# BRAINS.net
KiCad netlist of a schematic drawn in Altium Designer
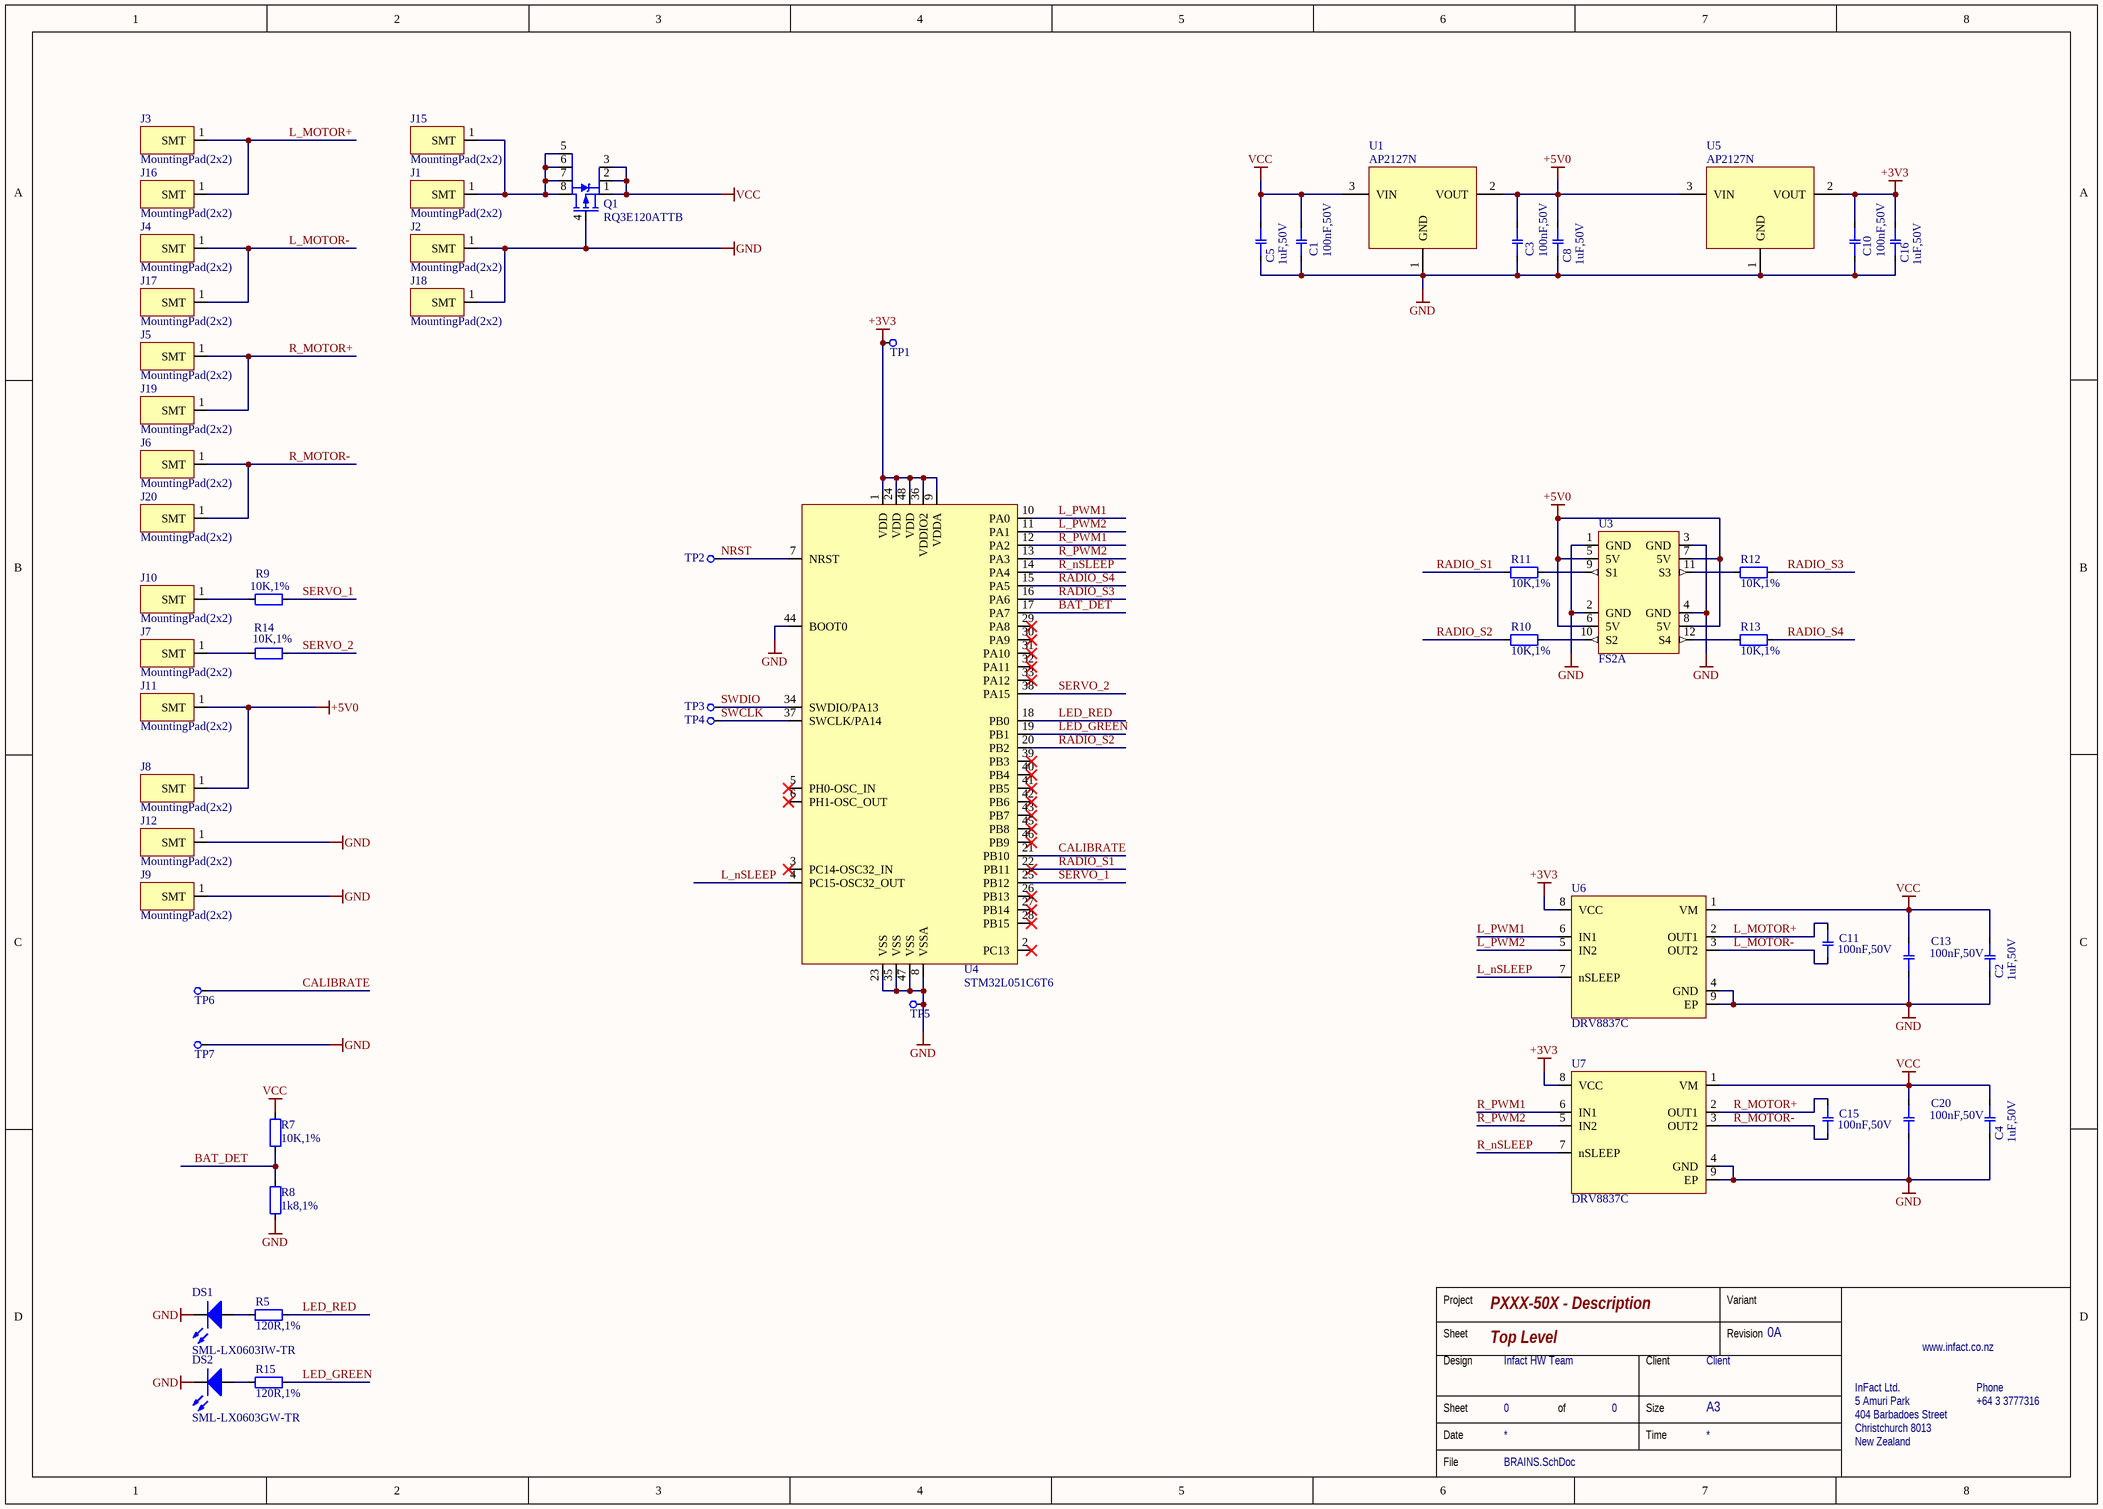
[diagram p0: BRAINS.SchDoc]

(export (version "E")
  (design (tool "Eeschema 10.0.6"))
  (components
    (comp (ref "C1")
      (value "100nF,50V")
      (footprint "CAPC1005X05N_0402")
      (description "CAP CER 100nF 50V X7R 0402")
      (fields (field (name "MANUFACTURER") "Taiyo Yuden") (field (name "TOLERANCE") "10%"))
      (libsource (lib "library") (part "CAP-NP_1"))
    )
    (comp (ref "C2")
      (value "1uF,50V")
      (footprint "CAPC1005X05N_0402")
      (description "CAP CER 1UF 50V X5R 0402")
      (fields (field (name "MANUFACTURER") "Taiyo Yuden") (field (name "TOLERANCE") "20%"))
      (libsource (lib "library") (part "CAP-NP_1"))
    )
    (comp (ref "C3")
      (value "100nF,50V")
      (footprint "CAPC1005X05N_0402")
      (description "CAP CER 100nF 50V X7R 0402")
      (fields (field (name "MANUFACTURER") "Taiyo Yuden") (field (name "TOLERANCE") "10%"))
      (libsource (lib "library") (part "CAP-NP_1"))
    )
    (comp (ref "C4")
      (value "1uF,50V")
      (footprint "CAPC1005X05N_0402")
      (description "CAP CER 1UF 50V X5R 0402")
      (fields (field (name "MANUFACTURER") "Taiyo Yuden") (field (name "TOLERANCE") "20%"))
      (libsource (lib "library") (part "CAP-NP_1"))
    )
    (comp (ref "C5")
      (value "1uF,50V")
      (footprint "CAPC1005X05N_0402")
      (description "CAP CER 1UF 50V X5R 0402")
      (fields (field (name "MANUFACTURER") "Taiyo Yuden") (field (name "TOLERANCE") "20%"))
      (libsource (lib "library") (part "CAP-NP_1"))
    )
    (comp (ref "C8")
      (value "1uF,50V")
      (footprint "CAPC1005X05N_0402")
      (description "CAP CER 1UF 50V X5R 0402")
      (fields (field (name "MANUFACTURER") "Taiyo Yuden") (field (name "TOLERANCE") "20%"))
      (libsource (lib "library") (part "CAP-NP_1"))
    )
    (comp (ref "C10")
      (value "100nF,50V")
      (footprint "CAPC1005X05N_0402")
      (description "CAP CER 100nF 50V X7R 0402")
      (fields (field (name "MANUFACTURER") "Taiyo Yuden") (field (name "TOLERANCE") "10%"))
      (libsource (lib "library") (part "CAP-NP_1"))
    )
    (comp (ref "C11")
      (value "100nF,50V")
      (footprint "CAPC1005X05N_0402")
      (description "CAP CER 100nF 50V X7R 0402")
      (fields (field (name "MANUFACTURER") "Taiyo Yuden") (field (name "TOLERANCE") "10%"))
      (libsource (lib "library") (part "CAP-NP_1"))
    )
    (comp (ref "C13")
      (value "100nF,50V")
      (footprint "CAPC1005X05N_0402")
      (description "CAP CER 100nF 50V X7R 0402")
      (fields (field (name "MANUFACTURER") "Taiyo Yuden") (field (name "TOLERANCE") "10%"))
      (libsource (lib "library") (part "CAP-NP_1"))
    )
    (comp (ref "C15")
      (value "100nF,50V")
      (footprint "CAPC1005X05N_0402")
      (description "CAP CER 100nF 50V X7R 0402")
      (fields (field (name "MANUFACTURER") "Taiyo Yuden") (field (name "TOLERANCE") "10%"))
      (libsource (lib "library") (part "CAP-NP_1"))
    )
    (comp (ref "C16")
      (value "1uF,50V")
      (footprint "CAPC1005X05N_0402")
      (description "CAP CER 1UF 50V X5R 0402")
      (fields (field (name "MANUFACTURER") "Taiyo Yuden") (field (name "TOLERANCE") "20%"))
      (libsource (lib "library") (part "CAP-NP_1"))
    )
    (comp (ref "C20")
      (value "100nF,50V")
      (footprint "CAPC1005X05N_0402")
      (description "CAP CER 100nF 50V X7R 0402")
      (fields (field (name "MANUFACTURER") "Taiyo Yuden") (field (name "TOLERANCE") "10%"))
      (libsource (lib "library") (part "CAP-NP_1"))
    )
    (comp (ref "DS1")
      (value "SML-LX0603IW-TR")
      (footprint "LED_SML-LX0603")
      (description "LED 635NM RED DIFF 0603 SMD")
      (fields (field (name "MANUFACTURER") "Lumex Opto/Components Inc"))
      (libsource (lib "library") (part "LED_1"))
    )
    (comp (ref "DS2")
      (value "SML-LX0603GW-TR")
      (footprint "LED_SML-LX0603")
      (description "LED 565NM GRN DIFF 0603 SMD")
      (fields (field (name "MANUFACTURER") "Lumex Opto/Components Inc"))
      (libsource (lib "library") (part "LED_1"))
    )
    (comp (ref "J1")
      (value "MountingPad(2x2)")
      (footprint "MountingPad(2x2)")
      (libsource (lib "") (part "MountingPad(2x2)_1"))
    )
    (comp (ref "J2")
      (value "MountingPad(2x2)")
      (footprint "MountingPad(2x2)")
      (libsource (lib "") (part "MountingPad(2x2)_1"))
    )
    (comp (ref "J3")
      (value "MountingPad(2x2)")
      (footprint "MountingPad(2x2)")
      (libsource (lib "Schlib1") (part "MountingPad(2x2)"))
    )
    (comp (ref "J4")
      (value "MountingPad(2x2)")
      (footprint "MountingPad(2x2)")
      (libsource (lib "Schlib1") (part "MountingPad(2x2)"))
    )
    (comp (ref "J5")
      (value "MountingPad(2x2)")
      (footprint "MountingPad(2x2)")
      (libsource (lib "Schlib1") (part "MountingPad(2x2)"))
    )
    (comp (ref "J6")
      (value "MountingPad(2x2)")
      (footprint "MountingPad(2x2)")
      (libsource (lib "Schlib1") (part "MountingPad(2x2)"))
    )
    (comp (ref "J7")
      (value "MountingPad(2x2)")
      (footprint "MountingPad(2x2)")
      (libsource (lib "Schlib1") (part "MountingPad(2x2)"))
    )
    (comp (ref "J8")
      (value "MountingPad(2x2)")
      (footprint "MountingPad(2x2)")
      (libsource (lib "Schlib1") (part "MountingPad(2x2)"))
    )
    (comp (ref "J9")
      (value "MountingPad(2x2)")
      (footprint "MountingPad(2x2)")
      (libsource (lib "Schlib1") (part "MountingPad(2x2)"))
    )
    (comp (ref "J10")
      (value "MountingPad(2x2)")
      (footprint "MountingPad(2x2)")
      (libsource (lib "Schlib1") (part "MountingPad(2x2)"))
    )
    (comp (ref "J11")
      (value "MountingPad(2x2)")
      (footprint "MountingPad(2x2)")
      (libsource (lib "Schlib1") (part "MountingPad(2x2)"))
    )
    (comp (ref "J12")
      (value "MountingPad(2x2)")
      (footprint "MountingPad(2x2)")
      (libsource (lib "Schlib1") (part "MountingPad(2x2)"))
    )
    (comp (ref "J15")
      (value "MountingPad(2x2)")
      (footprint "MountingPad(2x2)")
      (libsource (lib "Schlib1") (part "MountingPad(2x2)"))
    )
    (comp (ref "J16")
      (value "MountingPad(2x2)")
      (footprint "MountingPad(2x2)")
      (libsource (lib "Schlib1") (part "MountingPad(2x2)"))
    )
    (comp (ref "J17")
      (value "MountingPad(2x2)")
      (footprint "MountingPad(2x2)")
      (libsource (lib "Schlib1") (part "MountingPad(2x2)"))
    )
    (comp (ref "J18")
      (value "MountingPad(2x2)")
      (footprint "MountingPad(2x2)")
      (libsource (lib "Schlib1") (part "MountingPad(2x2)"))
    )
    (comp (ref "J19")
      (value "MountingPad(2x2)")
      (footprint "MountingPad(2x2)")
      (libsource (lib "Schlib1") (part "MountingPad(2x2)"))
    )
    (comp (ref "J20")
      (value "MountingPad(2x2)")
      (footprint "MountingPad(2x2)")
      (libsource (lib "Schlib1") (part "MountingPad(2x2)"))
    )
    (comp (ref "Q1")
      (value "RQ3E120ATTB")
      (footprint "ROHM-HSMT8")
      (description "MOSFET P-CH 30V 12A 8HSMT")
      (fields (field (name "MANUFACTURER") "Rohm Semiconductor"))
      (libsource (lib "library") (part "MOSFET-P_5"))
    )
    (comp (ref "R5")
      (value "120R,1%")
      (footprint "RESC1005X04N_0402")
      (description "RES 120 OHM 1/16W 0402 SMD")
      (fields (field (name "MANUFACTURER") "Yageo") (field (name "POWER") "0.0625W"))
      (libsource (lib "library") (part "RESISTOR_1"))
    )
    (comp (ref "R7")
      (value "10K,1%")
      (footprint "RESC1005X04N_0402")
      (description "RES 10K OHM 1/16W 1% 0402 SMD")
      (fields (field (name "MANUFACTURER") "Yageo") (field (name "POWER") "0.0625W"))
      (libsource (lib "") (part "RESISTOR_1_1"))
    )
    (comp (ref "R8")
      (value "1k8,1%")
      (footprint "RESC1005X04N_0402")
      (description "RES 1k8 0.0625W 1% 0402 SMD")
      (fields (field (name "MANUFACTURER") "Vishay Dale") (field (name "POWER") "0.0625W"))
      (libsource (lib "") (part "RESISTOR_1_1"))
    )
    (comp (ref "R9")
      (value "10K,1%")
      (footprint "RESC1005X04N_0402")
      (description "RES 10K OHM 1/16W 1% 0402 SMD")
      (fields (field (name "MANUFACTURER") "Yageo") (field (name "POWER") "0.0625W"))
      (libsource (lib "") (part "RESISTOR_1_1"))
    )
    (comp (ref "R10")
      (value "10K,1%")
      (footprint "RESC1005X04N_0402")
      (description "RES 10K OHM 1/16W 1% 0402 SMD")
      (fields (field (name "MANUFACTURER") "Yageo") (field (name "POWER") "0.0625W"))
      (libsource (lib "library") (part "RESISTOR_1"))
    )
    (comp (ref "R11")
      (value "10K,1%")
      (footprint "RESC1005X04N_0402")
      (description "RES 10K OHM 1/16W 1% 0402 SMD")
      (fields (field (name "MANUFACTURER") "Yageo") (field (name "POWER") "0.0625W"))
      (libsource (lib "library") (part "RESISTOR_1"))
    )
    (comp (ref "R12")
      (value "10K,1%")
      (footprint "RESC1005X04N_0402")
      (description "RES 10K OHM 1/16W 1% 0402 SMD")
      (fields (field (name "MANUFACTURER") "Yageo") (field (name "POWER") "0.0625W"))
      (libsource (lib "library") (part "RESISTOR_1"))
    )
    (comp (ref "R13")
      (value "10K,1%")
      (footprint "RESC1005X04N_0402")
      (description "RES 10K OHM 1/16W 1% 0402 SMD")
      (fields (field (name "MANUFACTURER") "Yageo") (field (name "POWER") "0.0625W"))
      (libsource (lib "library") (part "RESISTOR_1"))
    )
    (comp (ref "R14")
      (value "10K,1%")
      (footprint "RESC1005X04N_0402")
      (description "RES 10K OHM 1/16W 1% 0402 SMD")
      (fields (field (name "MANUFACTURER") "Yageo") (field (name "POWER") "0.0625W"))
      (libsource (lib "") (part "RESISTOR_1_1"))
    )
    (comp (ref "R15")
      (value "120R,1%")
      (footprint "RESC1005X04N_0402")
      (description "RES 120 OHM 1/16W 0402 SMD")
      (fields (field (name "MANUFACTURER") "Yageo") (field (name "POWER") "0.0625W"))
      (libsource (lib "library") (part "RESISTOR_1"))
    )
    (comp (ref "TP1")
      (value "TP_SMT")
      (footprint "TP_100")
      (description "Test Point - SMT")
      (libsource (lib "library") (part "TP_1"))
    )
    (comp (ref "TP2")
      (value "TP_SMT")
      (footprint "TP_100")
      (description "Test Point - SMT")
      (libsource (lib "library") (part "TP_1"))
    )
    (comp (ref "TP3")
      (value "TP_SMT")
      (footprint "TP_100")
      (description "Test Point - SMT")
      (libsource (lib "library") (part "TP_1"))
    )
    (comp (ref "TP4")
      (value "TP_SMT")
      (footprint "TP_100")
      (description "Test Point - SMT")
      (libsource (lib "library") (part "TP_1"))
    )
    (comp (ref "TP5")
      (value "TP_SMT")
      (footprint "TP_100")
      (description "Test Point - SMT")
      (libsource (lib "library") (part "TP_1"))
    )
    (comp (ref "TP6")
      (value "TP_SMT")
      (footprint "TP_100")
      (description "Test Point - SMT")
      (libsource (lib "library") (part "TP_1"))
    )
    (comp (ref "TP7")
      (value "TP_SMT")
      (footprint "TP_100")
      (description "Test Point - SMT")
      (libsource (lib "library") (part "TP_1"))
    )
    (comp (ref "U1")
      (value "AP2127N")
      (footprint "SOT95P237X112-3N_SOT23")
      (description "IC REG LINEAR 3.3V 300MA SOT23")
      (fields
        (field (name "MANUFACTURER") "Diodes Incorporated")
        (field (name "MANUFACTURER PART NUMBER") "AP2127N-3.3TRG1")
      )
      (libsource (lib "library") (part "AP2127N-3.3TRG1"))
    )
    (comp (ref "U3") (value "FS2A") (footprint "FS2A") (libsource (lib "Schlib1") (part "FS2A")))
    (comp (ref "U4")
      (value "STM32L051C6T6")
      (footprint "TSQFP50P900X900X160-48N_48LQFP")
      (description "IC MCU 32BIT 32KB FLASH 48LQFP")
      (fields (field (name "MANUFACTURER") "STMicroelectronics"))
      (libsource (lib "library") (part "STM32L051_48"))
    )
    (comp (ref "U5")
      (value "AP2127N")
      (footprint "SOT95P237X112-3N_SOT23")
      (description "IC REG LINEAR 3.3V 300MA SOT23")
      (fields
        (field (name "MANUFACTURER") "Diodes Incorporated")
        (field (name "MANUFACTURER PART NUMBER") "AP2127N-3.3TRG1")
      )
      (libsource (lib "library") (part "AP2127N-3.3TRG1"))
    )
    (comp (ref "U6")
      (value "DRV8837C")
      (footprint "DFN50P200X200X80-8N")
      (description "IC HALF-BRIDGE DRVR PWM 8WSON")
      (fields
        (field (name "MANUFACTURER") "Texas Instruments")
        (field (name "MANUFACTURER PART NUMBER") "DRV8837CDSGR")
      )
      (libsource (lib "library") (part "DRV8837C"))
    )
    (comp (ref "U7")
      (value "DRV8837C")
      (footprint "DFN50P200X200X80-8N")
      (description "IC HALF-BRIDGE DRVR PWM 8WSON")
      (fields
        (field (name "MANUFACTURER") "Texas Instruments")
        (field (name "MANUFACTURER PART NUMBER") "DRV8837CDSGR")
      )
      (libsource (lib "library") (part "DRV8837C"))
    )
  )
  (nets
    (net (code "1") (name "+3V3") (class "Default")
      (node (ref "C10") (pin "2") (pinfunction "2_2") (pintype "passive"))
      (node (ref "C16") (pin "2") (pinfunction "2_2") (pintype "passive"))
      (node (ref "TP1") (pin "1") (pinfunction "1_1") (pintype "passive"))
      (node (ref "U4") (pin "1") (pinfunction "VDD_1") (pintype "passive"))
      (node (ref "U4") (pin "24") (pinfunction "VDD_24") (pintype "passive"))
      (node (ref "U4") (pin "36") (pinfunction "VDDIO2_36") (pintype "passive"))
      (node (ref "U4") (pin "48") (pinfunction "VDD_48") (pintype "passive"))
      (node (ref "U4") (pin "9") (pinfunction "VDDA_9") (pintype "passive"))
      (node (ref "U5") (pin "2") (pinfunction "VOUT_2") (pintype "passive"))
      (node (ref "U6") (pin "8") (pinfunction "VCC_8") (pintype "passive"))
      (node (ref "U7") (pin "8") (pinfunction "VCC_8") (pintype "passive"))
    )
    (net (code "2") (name "+5V0") (class "Default")
      (node (ref "C3") (pin "2") (pinfunction "2_2") (pintype "passive"))
      (node (ref "C8") (pin "2") (pinfunction "2_2") (pintype "passive"))
      (node (ref "J11") (pin "1") (pinfunction "SMT_1") (pintype "passive"))
      (node (ref "J8") (pin "1") (pinfunction "SMT_1") (pintype "passive"))
      (node (ref "U1") (pin "2") (pinfunction "VOUT_2") (pintype "passive"))
      (node (ref "U3") (pin "5") (pinfunction "5V_5") (pintype "power_in"))
      (node (ref "U3") (pin "6") (pinfunction "5V_6") (pintype "power_in"))
      (node (ref "U3") (pin "7") (pinfunction "5V_7") (pintype "power_in"))
      (node (ref "U3") (pin "8") (pinfunction "5V_8") (pintype "power_in"))
      (node (ref "U5") (pin "3") (pinfunction "VIN_3") (pintype "passive"))
    )
    (net (code "3") (name "/BAT_DET") (class "Default")
      (node (ref "R7") (pin "2") (pinfunction "2_2") (pintype "passive"))
      (node (ref "R8") (pin "1") (pinfunction "1_1") (pintype "passive"))
      (node (ref "U4") (pin "17") (pinfunction "PA7_17") (pintype "passive"))
    )
    (net (code "4") (name "/CALIBRATE") (class "Default")
      (node (ref "TP6") (pin "1") (pinfunction "1_1") (pintype "passive"))
      (node (ref "U4") (pin "21") (pinfunction "PB10_21") (pintype "passive"))
    )
    (net (code "5") (name "/LED_GREEN") (class "Default")
      (node (ref "R15") (pin "2") (pinfunction "2_2") (pintype "passive"))
      (node (ref "U4") (pin "19") (pinfunction "PB1_19") (pintype "passive"))
    )
    (net (code "6") (name "/LED_RED") (class "Default")
      (node (ref "R5") (pin "2") (pinfunction "2_2") (pintype "passive"))
      (node (ref "U4") (pin "18") (pinfunction "PB0_18") (pintype "passive"))
    )
    (net (code "7") (name "/L_MOTOR+") (class "Default")
      (node (ref "C11") (pin "2") (pinfunction "2_2") (pintype "passive"))
      (node (ref "J16") (pin "1") (pinfunction "SMT_1") (pintype "passive"))
      (node (ref "J3") (pin "1") (pinfunction "SMT_1") (pintype "passive"))
      (node (ref "U6") (pin "2") (pinfunction "OUT1_2") (pintype "passive"))
    )
    (net (code "8") (name "/L_MOTOR-") (class "Default")
      (node (ref "C11") (pin "1") (pinfunction "1_1") (pintype "passive"))
      (node (ref "J17") (pin "1") (pinfunction "SMT_1") (pintype "passive"))
      (node (ref "J4") (pin "1") (pinfunction "SMT_1") (pintype "passive"))
      (node (ref "U6") (pin "3") (pinfunction "OUT2_3") (pintype "passive"))
    )
    (net (code "9") (name "/L_PWM1") (class "Default")
      (node (ref "U4") (pin "10") (pinfunction "PA0_10") (pintype "passive"))
      (node (ref "U6") (pin "6") (pinfunction "IN1_6") (pintype "passive"))
    )
    (net (code "10") (name "/L_PWM2") (class "Default")
      (node (ref "U4") (pin "11") (pinfunction "PA1_11") (pintype "passive"))
      (node (ref "U6") (pin "5") (pinfunction "IN2_5") (pintype "passive"))
    )
    (net (code "11") (name "/L_nSLEEP") (class "Default")
      (node (ref "U4") (pin "4") (pinfunction "PC15-OSC32_OUT_4") (pintype "passive"))
      (node (ref "U6") (pin "7") (pinfunction "nSLEEP_7") (pintype "passive"))
    )
    (net (code "12") (name "/NRST") (class "Default")
      (node (ref "TP2") (pin "1") (pinfunction "1_1") (pintype "passive"))
      (node (ref "U4") (pin "7") (pinfunction "NRST_7") (pintype "passive"))
    )
    (net (code "13") (name "/RADIO_S1") (class "Default")
      (node (ref "R11") (pin "1") (pinfunction "1_1") (pintype "passive"))
      (node (ref "U4") (pin "22") (pinfunction "PB11_22") (pintype "passive"))
    )
    (net (code "14") (name "/RADIO_S2") (class "Default")
      (node (ref "R10") (pin "1") (pinfunction "1_1") (pintype "passive"))
      (node (ref "U4") (pin "20") (pinfunction "PB2_20") (pintype "passive"))
    )
    (net (code "15") (name "/RADIO_S3") (class "Default")
      (node (ref "R12") (pin "2") (pinfunction "2_2") (pintype "passive"))
      (node (ref "U4") (pin "16") (pinfunction "PA6_16") (pintype "passive"))
    )
    (net (code "16") (name "/RADIO_S4") (class "Default")
      (node (ref "R13") (pin "2") (pinfunction "2_2") (pintype "passive"))
      (node (ref "U4") (pin "15") (pinfunction "PA5_15") (pintype "passive"))
    )
    (net (code "17") (name "/R_MOTOR+") (class "Default")
      (node (ref "C15") (pin "2") (pinfunction "2_2") (pintype "passive"))
      (node (ref "J19") (pin "1") (pinfunction "SMT_1") (pintype "passive"))
      (node (ref "J5") (pin "1") (pinfunction "SMT_1") (pintype "passive"))
      (node (ref "U7") (pin "2") (pinfunction "OUT1_2") (pintype "passive"))
    )
    (net (code "18") (name "/R_MOTOR-") (class "Default")
      (node (ref "C15") (pin "1") (pinfunction "1_1") (pintype "passive"))
      (node (ref "J20") (pin "1") (pinfunction "SMT_1") (pintype "passive"))
      (node (ref "J6") (pin "1") (pinfunction "SMT_1") (pintype "passive"))
      (node (ref "U7") (pin "3") (pinfunction "OUT2_3") (pintype "passive"))
    )
    (net (code "19") (name "/R_PWM1") (class "Default")
      (node (ref "U4") (pin "12") (pinfunction "PA2_12") (pintype "passive"))
      (node (ref "U7") (pin "6") (pinfunction "IN1_6") (pintype "passive"))
    )
    (net (code "20") (name "/R_PWM2") (class "Default")
      (node (ref "U4") (pin "13") (pinfunction "PA3_13") (pintype "passive"))
      (node (ref "U7") (pin "5") (pinfunction "IN2_5") (pintype "passive"))
    )
    (net (code "21") (name "/R_nSLEEP") (class "Default")
      (node (ref "U4") (pin "14") (pinfunction "PA4_14") (pintype "passive"))
      (node (ref "U7") (pin "7") (pinfunction "nSLEEP_7") (pintype "passive"))
    )
    (net (code "22") (name "/SERVO_1") (class "Default")
      (node (ref "R9") (pin "1") (pinfunction "1_1") (pintype "passive"))
      (node (ref "U4") (pin "25") (pinfunction "PB12_25") (pintype "passive"))
    )
    (net (code "23") (name "/SERVO_2") (class "Default")
      (node (ref "R14") (pin "1") (pinfunction "1_1") (pintype "passive"))
      (node (ref "U4") (pin "38") (pinfunction "PA15_38") (pintype "passive"))
    )
    (net (code "24") (name "/SWCLK") (class "Default")
      (node (ref "TP4") (pin "1") (pinfunction "1_1") (pintype "passive"))
      (node (ref "U4") (pin "37") (pinfunction "SWCLK/PA14_37") (pintype "passive"))
    )
    (net (code "25") (name "/SWDIO") (class "Default")
      (node (ref "TP3") (pin "1") (pinfunction "1_1") (pintype "passive"))
      (node (ref "U4") (pin "34") (pinfunction "SWDIO/PA13_34") (pintype "passive"))
    )
    (net (code "26") (name "GND") (class "Default")
      (node (ref "C1") (pin "1") (pinfunction "1_1") (pintype "passive"))
      (node (ref "C10") (pin "1") (pinfunction "1_1") (pintype "passive"))
      (node (ref "C13") (pin "1") (pinfunction "1_1") (pintype "passive"))
      (node (ref "C16") (pin "1") (pinfunction "1_1") (pintype "passive"))
      (node (ref "C2") (pin "1") (pinfunction "1_1") (pintype "passive"))
      (node (ref "C20") (pin "1") (pinfunction "1_1") (pintype "passive"))
      (node (ref "C3") (pin "1") (pinfunction "1_1") (pintype "passive"))
      (node (ref "C4") (pin "1") (pinfunction "1_1") (pintype "passive"))
      (node (ref "C5") (pin "1") (pinfunction "1_1") (pintype "passive"))
      (node (ref "C8") (pin "1") (pinfunction "1_1") (pintype "passive"))
      (node (ref "DS1") (pin "1") (pinfunction "C_1") (pintype "passive"))
      (node (ref "DS2") (pin "1") (pinfunction "C_1") (pintype "passive"))
      (node (ref "J12") (pin "1") (pinfunction "SMT_1") (pintype "passive"))
      (node (ref "J18") (pin "1") (pinfunction "SMT_1") (pintype "passive"))
      (node (ref "J2") (pin "1") (pinfunction "SMT_1") (pintype "passive"))
      (node (ref "J9") (pin "1") (pinfunction "SMT_1") (pintype "passive"))
      (node (ref "Q1") (pin "4") (pinfunction "G_4") (pintype "passive"))
      (node (ref "R8") (pin "2") (pinfunction "2_2") (pintype "passive"))
      (node (ref "TP5") (pin "1") (pinfunction "1_1") (pintype "passive"))
      (node (ref "TP7") (pin "1") (pinfunction "1_1") (pintype "passive"))
      (node (ref "U1") (pin "1") (pinfunction "GND_1") (pintype "passive"))
      (node (ref "U3") (pin "1") (pinfunction "GND_1") (pintype "power_in"))
      (node (ref "U3") (pin "2") (pinfunction "GND_2") (pintype "power_in"))
      (node (ref "U3") (pin "3") (pinfunction "GND_3") (pintype "power_in"))
      (node (ref "U3") (pin "4") (pinfunction "GND_4") (pintype "power_in"))
      (node (ref "U4") (pin "23") (pinfunction "VSS_23") (pintype "passive"))
      (node (ref "U4") (pin "35") (pinfunction "VSS_35") (pintype "passive"))
      (node (ref "U4") (pin "44") (pinfunction "BOOT0_44") (pintype "passive"))
      (node (ref "U4") (pin "47") (pinfunction "VSS_47") (pintype "passive"))
      (node (ref "U4") (pin "8") (pinfunction "VSSA_8") (pintype "passive"))
      (node (ref "U5") (pin "1") (pinfunction "GND_1") (pintype "passive"))
      (node (ref "U6") (pin "4") (pinfunction "GND_4") (pintype "passive"))
      (node (ref "U6") (pin "9") (pinfunction "EP_9") (pintype "passive"))
      (node (ref "U7") (pin "4") (pinfunction "GND_4") (pintype "passive"))
      (node (ref "U7") (pin "9") (pinfunction "EP_9") (pintype "passive"))
    )
    (net (code "27") (name "Net-(DS1-A)") (class "Default")
      (node (ref "DS1") (pin "2") (pinfunction "A_2") (pintype "passive"))
      (node (ref "R5") (pin "1") (pinfunction "1_1") (pintype "passive"))
    )
    (net (code "28") (name "Net-(DS2-A)") (class "Default")
      (node (ref "DS2") (pin "2") (pinfunction "A_2") (pintype "passive"))
      (node (ref "R15") (pin "1") (pinfunction "1_1") (pintype "passive"))
    )
    (net (code "29") (name "Net-(J1-SMT)") (class "Default")
      (node (ref "J1") (pin "1") (pinfunction "SMT_1") (pintype "passive"))
      (node (ref "J15") (pin "1") (pinfunction "SMT_1") (pintype "passive"))
      (node (ref "Q1") (pin "5") (pinfunction "D_5") (pintype "passive"))
      (node (ref "Q1") (pin "6") (pinfunction "D_6") (pintype "passive"))
      (node (ref "Q1") (pin "7") (pinfunction "D_7") (pintype "passive"))
      (node (ref "Q1") (pin "8") (pinfunction "D_8") (pintype "passive"))
    )
    (net (code "30") (name "Net-(J7-SMT)") (class "Default")
      (node (ref "J7") (pin "1") (pinfunction "SMT_1") (pintype "passive"))
      (node (ref "R14") (pin "2") (pinfunction "2_2") (pintype "passive"))
    )
    (net (code "31") (name "Net-(J10-SMT)") (class "Default")
      (node (ref "J10") (pin "1") (pinfunction "SMT_1") (pintype "passive"))
      (node (ref "R9") (pin "2") (pinfunction "2_2") (pintype "passive"))
    )
    (net (code "32") (name "Net-(U3-S1)") (class "Default")
      (node (ref "R11") (pin "2") (pinfunction "2_2") (pintype "passive"))
      (node (ref "U3") (pin "9") (pinfunction "S1_9") (pintype "output"))
    )
    (net (code "33") (name "Net-(U3-S2)") (class "Default")
      (node (ref "R10") (pin "2") (pinfunction "2_2") (pintype "passive"))
      (node (ref "U3") (pin "10") (pinfunction "S2_10") (pintype "output"))
    )
    (net (code "34") (name "Net-(U3-S3)") (class "Default")
      (node (ref "R12") (pin "1") (pinfunction "1_1") (pintype "passive"))
      (node (ref "U3") (pin "11") (pinfunction "S3_11") (pintype "output"))
    )
    (net (code "35") (name "Net-(U3-S4)") (class "Default")
      (node (ref "R13") (pin "1") (pinfunction "1_1") (pintype "passive"))
      (node (ref "U3") (pin "12") (pinfunction "S4_12") (pintype "output"))
    )
    (net (code "36") (name "VCC") (class "Default")
      (node (ref "C1") (pin "2") (pinfunction "2_2") (pintype "passive"))
      (node (ref "C13") (pin "2") (pinfunction "2_2") (pintype "passive"))
      (node (ref "C2") (pin "2") (pinfunction "2_2") (pintype "passive"))
      (node (ref "C20") (pin "2") (pinfunction "2_2") (pintype "passive"))
      (node (ref "C4") (pin "2") (pinfunction "2_2") (pintype "passive"))
      (node (ref "C5") (pin "2") (pinfunction "2_2") (pintype "passive"))
      (node (ref "Q1") (pin "1") (pinfunction "S_1") (pintype "passive"))
      (node (ref "Q1") (pin "2") (pinfunction "S_2") (pintype "passive"))
      (node (ref "Q1") (pin "3") (pinfunction "S_3") (pintype "passive"))
      (node (ref "R7") (pin "1") (pinfunction "1_1") (pintype "passive"))
      (node (ref "U1") (pin "3") (pinfunction "VIN_3") (pintype "passive"))
      (node (ref "U6") (pin "1") (pinfunction "VM_1") (pintype "passive"))
      (node (ref "U7") (pin "1") (pinfunction "VM_1") (pintype "passive"))
    )
    (net (code "37") (name "unconnected-(U4-PA8-Pad29)") (class "Default")
      (node (ref "U4") (pin "29") (pinfunction "PA8_29") (pintype "passive+no_connect"))
    )
    (net (code "38") (name "unconnected-(U4-PA9-Pad30)") (class "Default")
      (node (ref "U4") (pin "30") (pinfunction "PA9_30") (pintype "passive+no_connect"))
    )
    (net (code "39") (name "unconnected-(U4-PA10-Pad31)") (class "Default")
      (node (ref "U4") (pin "31") (pinfunction "PA10_31") (pintype "passive+no_connect"))
    )
    (net (code "40") (name "unconnected-(U4-PA11-Pad32)") (class "Default")
      (node (ref "U4") (pin "32") (pinfunction "PA11_32") (pintype "passive+no_connect"))
    )
    (net (code "41") (name "unconnected-(U4-PA12-Pad33)") (class "Default")
      (node (ref "U4") (pin "33") (pinfunction "PA12_33") (pintype "passive+no_connect"))
    )
    (net (code "42") (name "unconnected-(U4-PB3-Pad39)") (class "Default")
      (node (ref "U4") (pin "39") (pinfunction "PB3_39") (pintype "passive+no_connect"))
    )
    (net (code "43") (name "unconnected-(U4-PB4-Pad40)") (class "Default")
      (node (ref "U4") (pin "40") (pinfunction "PB4_40") (pintype "passive+no_connect"))
    )
    (net (code "44") (name "unconnected-(U4-PB5-Pad41)") (class "Default")
      (node (ref "U4") (pin "41") (pinfunction "PB5_41") (pintype "passive+no_connect"))
    )
    (net (code "45") (name "unconnected-(U4-PB6-Pad42)") (class "Default")
      (node (ref "U4") (pin "42") (pinfunction "PB6_42") (pintype "passive+no_connect"))
    )
    (net (code "46") (name "unconnected-(U4-PB7-Pad43)") (class "Default")
      (node (ref "U4") (pin "43") (pinfunction "PB7_43") (pintype "passive+no_connect"))
    )
    (net (code "47") (name "unconnected-(U4-PB8-Pad45)") (class "Default")
      (node (ref "U4") (pin "45") (pinfunction "PB8_45") (pintype "passive+no_connect"))
    )
    (net (code "48") (name "unconnected-(U4-PB9-Pad46)") (class "Default")
      (node (ref "U4") (pin "46") (pinfunction "PB9_46") (pintype "passive+no_connect"))
    )
    (net (code "49") (name "unconnected-(U4-PB13-Pad26)") (class "Default")
      (node (ref "U4") (pin "26") (pinfunction "PB13_26") (pintype "passive+no_connect"))
    )
    (net (code "50") (name "unconnected-(U4-PB14-Pad27)") (class "Default")
      (node (ref "U4") (pin "27") (pinfunction "PB14_27") (pintype "passive+no_connect"))
    )
    (net (code "51") (name "unconnected-(U4-PB15-Pad28)") (class "Default")
      (node (ref "U4") (pin "28") (pinfunction "PB15_28") (pintype "passive+no_connect"))
    )
    (net (code "52") (name "unconnected-(U4-PC13-Pad2)") (class "Default")
      (node (ref "U4") (pin "2") (pinfunction "PC13_2") (pintype "passive+no_connect"))
    )
    (net (code "53") (name "unconnected-(U4-PC14-OSC32_IN-Pad3)") (class "Default")
      (node (ref "U4") (pin "3") (pinfunction "PC14-OSC32_IN_3") (pintype "passive+no_connect"))
    )
    (net (code "54") (name "unconnected-(U4-PH0-OSC_IN-Pad5)") (class "Default")
      (node (ref "U4") (pin "5") (pinfunction "PH0-OSC_IN_5") (pintype "passive+no_connect"))
    )
    (net (code "55") (name "unconnected-(U4-PH1-OSC_OUT-Pad6)") (class "Default")
      (node (ref "U4") (pin "6") (pinfunction "PH1-OSC_OUT_6") (pintype "passive+no_connect"))
    )
  )
)
